# k64f-kit.net
KiCad netlist of a schematic drawn in EAGLE
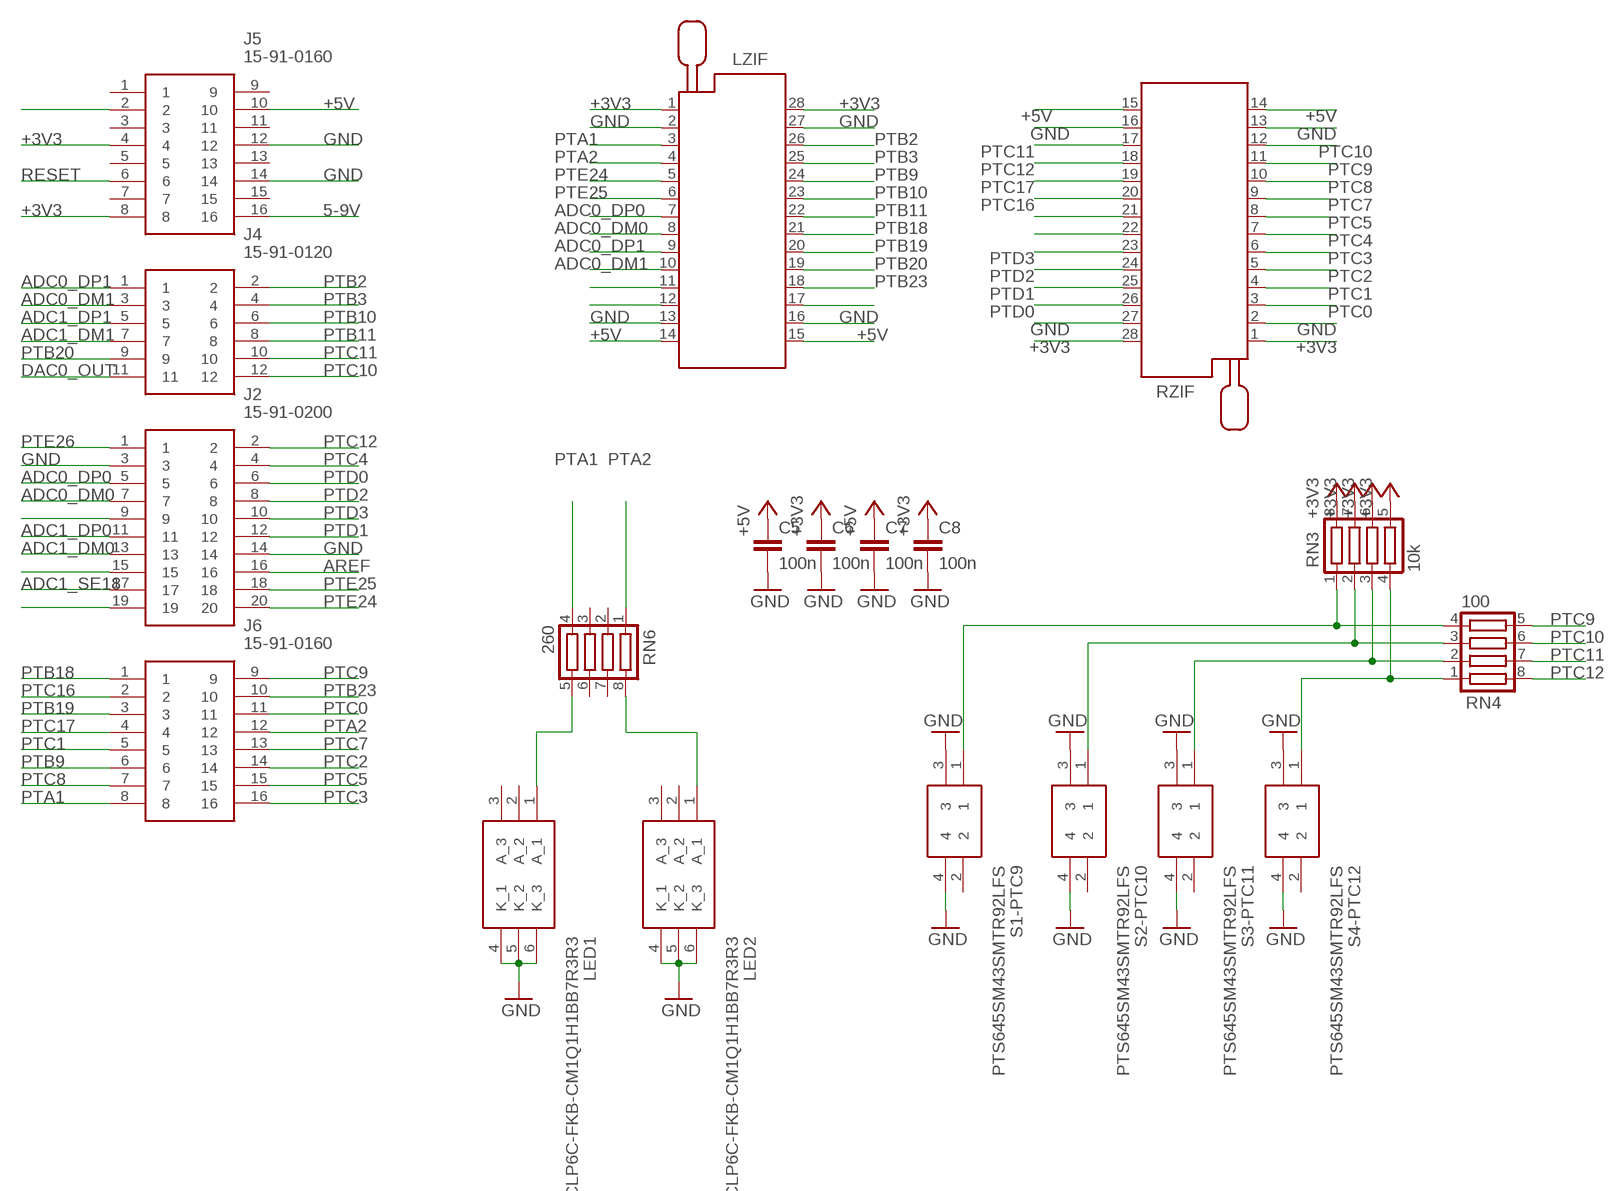
[diagram p0: schematic, sheet 1]

(export (version "E")
  (design (tool "Eeschema 10.0.6"))
  (components
    (comp (ref "C5")
      (value "100n")
      (footprint "eagle-import:C1206")
      (libsource (lib "eagle-import") (part "C-EUC1206"))
    )
    (comp (ref "C6")
      (value "100n")
      (footprint "eagle-import:C1206")
      (libsource (lib "eagle-import") (part "C-EUC1206"))
    )
    (comp (ref "C7")
      (value "100n")
      (footprint "eagle-import:C1206")
      (libsource (lib "eagle-import") (part "C-EUC1206"))
    )
    (comp (ref "C8")
      (value "100n")
      (footprint "eagle-import:C1206")
      (libsource (lib "eagle-import") (part "C-EUC1206"))
    )
    (comp (ref "J2")
      (value "15-91-0200")
      (footprint "eagle-import:15910200")
      (fields (field (name "MOUSER_PART_NUMBER") "538-15-91-0200"))
      (libsource (lib "eagle-import") (part "15-91-0200"))
    )
    (comp (ref "J4")
      (value "15-91-0120")
      (footprint "eagle-import:15910120")
      (fields (field (name "MOUSER_PART_NUMBER") "538-15-91-0120"))
      (libsource (lib "eagle-import") (part "15-91-0120"))
    )
    (comp (ref "J5")
      (value "15-91-0160")
      (footprint "eagle-import:15910160")
      (fields
        (field (name "MANUFACTURER_PART_NUMBER") "15-91-2160")
        (field (name "MOUSER_PART_NUMBER") "538-15-91-2160")
      )
      (libsource (lib "eagle-import") (part "15-91-0160"))
    )
    (comp (ref "J6")
      (value "15-91-0160")
      (footprint "eagle-import:15910160")
      (fields
        (field (name "MANUFACTURER_PART_NUMBER") "15-91-2160")
        (field (name "MOUSER_PART_NUMBER") "538-15-91-2160")
      )
      (libsource (lib "eagle-import") (part "15-91-0160"))
    )
    (comp (ref "LED1")
      (value "CLP6C-FKB-CM1Q1H1BB7R3R3")
      (footprint "eagle-import:CLP6CFKBCM1Q1H1BB7R3R3")
      (fields
        (field (name "MOUSER_PART_NUMBER") "941-P6CFKBCM1Q1H17R3")
        (field (name "RS_PART_NUMBER") "8106939P")
      )
      (libsource (lib "eagle-import") (part "CLP6C-FKB-CM1Q1H1BB7R3R3"))
    )
    (comp (ref "LED2")
      (value "CLP6C-FKB-CM1Q1H1BB7R3R3")
      (footprint "eagle-import:CLP6CFKBCM1Q1H1BB7R3R3")
      (fields
        (field (name "MOUSER_PART_NUMBER") "941-P6CFKBCM1Q1H17R3")
        (field (name "RS_PART_NUMBER") "8106939P")
      )
      (libsource (lib "eagle-import") (part "CLP6C-FKB-CM1Q1H1BB7R3R3"))
    )
    (comp (ref "LZIF")
      (value "228-22-602")
      (footprint "eagle-import:228-1277-00-0602J")
      (libsource (lib "eagle-import") (part "228-?22-602"))
    )
    (comp (ref "RN3")
      (value "10k")
      (footprint "eagle-import:CTS742C083")
      (libsource (lib "eagle-import") (part "CTS742C083"))
    )
    (comp (ref "RN4")
      (value "100")
      (footprint "eagle-import:CTS742C083")
      (libsource (lib "eagle-import") (part "CTS742C083"))
    )
    (comp (ref "RN6")
      (value "260")
      (footprint "eagle-import:CTS742C083")
      (libsource (lib "eagle-import") (part "CTS742C083"))
    )
    (comp (ref "RZIF")
      (value "228-22-602")
      (footprint "eagle-import:228-1277-00-0602J")
      (libsource (lib "eagle-import") (part "228-?22-602"))
    )
    (comp (ref "S1-PTC9")
      (value "PTS645SM43SMTR92LFS")
      (footprint "eagle-import:PTS645(SMT)")
      (fields (field (name "MOUSER_PART_NUMBER") "611-PTS645SM43SMTR92"))
      (libsource (lib "eagle-import") (part "PTS645SM43SMTR92LFS"))
    )
    (comp (ref "S2-PTC10")
      (value "PTS645SM43SMTR92LFS")
      (footprint "eagle-import:PTS645(SMT)")
      (fields (field (name "MOUSER_PART_NUMBER") "611-PTS645SM43SMTR92"))
      (libsource (lib "eagle-import") (part "PTS645SM43SMTR92LFS"))
    )
    (comp (ref "S3-PTC11")
      (value "PTS645SM43SMTR92LFS")
      (footprint "eagle-import:PTS645(SMT)")
      (fields (field (name "MOUSER_PART_NUMBER") "611-PTS645SM43SMTR92"))
      (libsource (lib "eagle-import") (part "PTS645SM43SMTR92LFS"))
    )
    (comp (ref "S4-PTC12")
      (value "PTS645SM43SMTR92LFS")
      (footprint "eagle-import:PTS645(SMT)")
      (fields (field (name "MOUSER_PART_NUMBER") "611-PTS645SM43SMTR92"))
      (libsource (lib "eagle-import") (part "PTS645SM43SMTR92LFS"))
    )
  )
  (nets
    (net (code "1") (name "+3V3") (class "Default")
      (node (ref "C6") (pin "1") (pinfunction "1_1") (pintype "passive"))
      (node (ref "C8") (pin "1") (pinfunction "1_1") (pintype "passive"))
      (node (ref "J5") (pin "4") (pinfunction "4_4") (pintype "bidirectional"))
      (node (ref "J5") (pin "8") (pinfunction "8_8") (pintype "bidirectional"))
      (node (ref "LZIF") (pin "1") (pinfunction "1_1") (pintype "passive"))
      (node (ref "LZIF") (pin "28") (pinfunction "28_28") (pintype "passive"))
      (node (ref "RN3") (pin "5") (pinfunction "5_5") (pintype "passive"))
      (node (ref "RN3") (pin "6") (pinfunction "6_6") (pintype "passive"))
      (node (ref "RN3") (pin "7") (pinfunction "7_7") (pintype "passive"))
      (node (ref "RN3") (pin "8") (pinfunction "8_8") (pintype "passive"))
      (node (ref "RZIF") (pin "1") (pinfunction "1_1") (pintype "passive"))
      (node (ref "RZIF") (pin "28") (pinfunction "28_28") (pintype "passive"))
    )
    (net (code "2") (name "+5V") (class "Default")
      (node (ref "C5") (pin "1") (pinfunction "1_1") (pintype "passive"))
      (node (ref "C7") (pin "1") (pinfunction "1_1") (pintype "passive"))
      (node (ref "J5") (pin "10") (pinfunction "10_10") (pintype "bidirectional"))
      (node (ref "LZIF") (pin "14") (pinfunction "14_14") (pintype "passive"))
      (node (ref "LZIF") (pin "15") (pinfunction "15_15") (pintype "passive"))
      (node (ref "RZIF") (pin "14") (pinfunction "14_14") (pintype "passive"))
      (node (ref "RZIF") (pin "15") (pinfunction "15_15") (pintype "passive"))
    )
    (net (code "3") (name "/5-9V") (class "Default")
      (node (ref "J5") (pin "16") (pinfunction "16_16") (pintype "bidirectional"))
    )
    (net (code "4") (name "/ADC0_DM0") (class "Default")
      (node (ref "J2") (pin "7") (pinfunction "7_7") (pintype "bidirectional"))
      (node (ref "LZIF") (pin "8") (pinfunction "8_8") (pintype "passive"))
    )
    (net (code "5") (name "/ADC0_DM1") (class "Default")
      (node (ref "J4") (pin "3") (pinfunction "3_3") (pintype "bidirectional"))
      (node (ref "LZIF") (pin "10") (pinfunction "10_10") (pintype "passive"))
    )
    (net (code "6") (name "/ADC0_DP0") (class "Default")
      (node (ref "J2") (pin "5") (pinfunction "5_5") (pintype "bidirectional"))
      (node (ref "LZIF") (pin "7") (pinfunction "7_7") (pintype "passive"))
    )
    (net (code "7") (name "/ADC0_DP1") (class "Default")
      (node (ref "J4") (pin "1") (pinfunction "1_1") (pintype "bidirectional"))
      (node (ref "LZIF") (pin "9") (pinfunction "9_9") (pintype "passive"))
    )
    (net (code "8") (name "/ADC1_DM0") (class "Default")
      (node (ref "J2") (pin "13") (pinfunction "13_13") (pintype "bidirectional"))
    )
    (net (code "9") (name "/ADC1_DM1") (class "Default")
      (node (ref "J4") (pin "7") (pinfunction "7_7") (pintype "bidirectional"))
    )
    (net (code "10") (name "/ADC1_DP0") (class "Default")
      (node (ref "J2") (pin "11") (pinfunction "11_11") (pintype "bidirectional"))
    )
    (net (code "11") (name "/ADC1_DP1") (class "Default")
      (node (ref "J4") (pin "5") (pinfunction "5_5") (pintype "bidirectional"))
    )
    (net (code "12") (name "/ADC1_SE18") (class "Default")
      (node (ref "J2") (pin "17") (pinfunction "17_17") (pintype "bidirectional"))
    )
    (net (code "13") (name "/AREF") (class "Default")
      (node (ref "J2") (pin "16") (pinfunction "16_16") (pintype "bidirectional"))
    )
    (net (code "14") (name "/DAC0_OUT") (class "Default")
      (node (ref "J4") (pin "11") (pinfunction "11_11") (pintype "bidirectional"))
    )
    (net (code "15") (name "/PTA1") (class "Default")
      (node (ref "J6") (pin "8") (pinfunction "8_8") (pintype "bidirectional"))
      (node (ref "LZIF") (pin "3") (pinfunction "3_3") (pintype "passive"))
      (node (ref "RN6") (pin "1") (pinfunction "1_1") (pintype "passive"))
    )
    (net (code "16") (name "/PTA2") (class "Default")
      (node (ref "J6") (pin "12") (pinfunction "12_12") (pintype "bidirectional"))
      (node (ref "LZIF") (pin "4") (pinfunction "4_4") (pintype "passive"))
      (node (ref "RN6") (pin "4") (pinfunction "4_4") (pintype "passive"))
    )
    (net (code "17") (name "/PTB2") (class "Default")
      (node (ref "J4") (pin "2") (pinfunction "2_2") (pintype "bidirectional"))
      (node (ref "LZIF") (pin "26") (pinfunction "26_26") (pintype "passive"))
    )
    (net (code "18") (name "/PTB3") (class "Default")
      (node (ref "J4") (pin "4") (pinfunction "4_4") (pintype "bidirectional"))
      (node (ref "LZIF") (pin "25") (pinfunction "25_25") (pintype "passive"))
    )
    (net (code "19") (name "/PTB9") (class "Default")
      (node (ref "J6") (pin "6") (pinfunction "6_6") (pintype "bidirectional"))
      (node (ref "LZIF") (pin "24") (pinfunction "24_24") (pintype "passive"))
    )
    (net (code "20") (name "/PTB10") (class "Default")
      (node (ref "J4") (pin "6") (pinfunction "6_6") (pintype "bidirectional"))
      (node (ref "LZIF") (pin "23") (pinfunction "23_23") (pintype "passive"))
    )
    (net (code "21") (name "/PTB11") (class "Default")
      (node (ref "J4") (pin "8") (pinfunction "8_8") (pintype "bidirectional"))
      (node (ref "LZIF") (pin "22") (pinfunction "22_22") (pintype "passive"))
    )
    (net (code "22") (name "/PTB18") (class "Default")
      (node (ref "J6") (pin "1") (pinfunction "1_1") (pintype "bidirectional"))
      (node (ref "LZIF") (pin "21") (pinfunction "21_21") (pintype "passive"))
    )
    (net (code "23") (name "/PTB19") (class "Default")
      (node (ref "J6") (pin "3") (pinfunction "3_3") (pintype "bidirectional"))
      (node (ref "LZIF") (pin "20") (pinfunction "20_20") (pintype "passive"))
    )
    (net (code "24") (name "/PTB20") (class "Default")
      (node (ref "J4") (pin "9") (pinfunction "9_9") (pintype "bidirectional"))
      (node (ref "LZIF") (pin "19") (pinfunction "19_19") (pintype "passive"))
    )
    (net (code "25") (name "/PTB23") (class "Default")
      (node (ref "J6") (pin "10") (pinfunction "10_10") (pintype "bidirectional"))
      (node (ref "LZIF") (pin "18") (pinfunction "18_18") (pintype "passive"))
    )
    (net (code "26") (name "/PTC0") (class "Default")
      (node (ref "J6") (pin "11") (pinfunction "11_11") (pintype "bidirectional"))
      (node (ref "RZIF") (pin "3") (pinfunction "3_3") (pintype "passive"))
    )
    (net (code "27") (name "/PTC1") (class "Default")
      (node (ref "J6") (pin "5") (pinfunction "5_5") (pintype "bidirectional"))
      (node (ref "RZIF") (pin "4") (pinfunction "4_4") (pintype "passive"))
    )
    (net (code "28") (name "/PTC2") (class "Default")
      (node (ref "J6") (pin "14") (pinfunction "14_14") (pintype "bidirectional"))
      (node (ref "RZIF") (pin "5") (pinfunction "5_5") (pintype "passive"))
    )
    (net (code "29") (name "/PTC3") (class "Default")
      (node (ref "J6") (pin "16") (pinfunction "16_16") (pintype "bidirectional"))
      (node (ref "RZIF") (pin "6") (pinfunction "6_6") (pintype "passive"))
    )
    (net (code "30") (name "/PTC4") (class "Default")
      (node (ref "J2") (pin "4") (pinfunction "4_4") (pintype "bidirectional"))
      (node (ref "RZIF") (pin "7") (pinfunction "7_7") (pintype "passive"))
    )
    (net (code "31") (name "/PTC5") (class "Default")
      (node (ref "J6") (pin "15") (pinfunction "15_15") (pintype "bidirectional"))
      (node (ref "RZIF") (pin "8") (pinfunction "8_8") (pintype "passive"))
    )
    (net (code "32") (name "/PTC7") (class "Default")
      (node (ref "J6") (pin "13") (pinfunction "13_13") (pintype "bidirectional"))
      (node (ref "RZIF") (pin "9") (pinfunction "9_9") (pintype "passive"))
    )
    (net (code "33") (name "/PTC8") (class "Default")
      (node (ref "J6") (pin "7") (pinfunction "7_7") (pintype "bidirectional"))
      (node (ref "RZIF") (pin "10") (pinfunction "10_10") (pintype "passive"))
    )
    (net (code "34") (name "/PTC9") (class "Default")
      (node (ref "J6") (pin "9") (pinfunction "9_9") (pintype "bidirectional"))
      (node (ref "RN4") (pin "5") (pinfunction "5_5") (pintype "passive"))
      (node (ref "RZIF") (pin "11") (pinfunction "11_11") (pintype "passive"))
    )
    (net (code "35") (name "/PTC10") (class "Default")
      (node (ref "J4") (pin "12") (pinfunction "12_12") (pintype "bidirectional"))
      (node (ref "RN4") (pin "6") (pinfunction "6_6") (pintype "passive"))
      (node (ref "RZIF") (pin "12") (pinfunction "12_12") (pintype "passive"))
    )
    (net (code "36") (name "/PTC11") (class "Default")
      (node (ref "J4") (pin "10") (pinfunction "10_10") (pintype "bidirectional"))
      (node (ref "RN4") (pin "7") (pinfunction "7_7") (pintype "passive"))
      (node (ref "RZIF") (pin "17") (pinfunction "17_17") (pintype "passive"))
    )
    (net (code "37") (name "/PTC12") (class "Default")
      (node (ref "J2") (pin "2") (pinfunction "2_2") (pintype "bidirectional"))
      (node (ref "RN4") (pin "8") (pinfunction "8_8") (pintype "passive"))
      (node (ref "RZIF") (pin "18") (pinfunction "18_18") (pintype "passive"))
    )
    (net (code "38") (name "/PTC16") (class "Default")
      (node (ref "J6") (pin "2") (pinfunction "2_2") (pintype "bidirectional"))
      (node (ref "RZIF") (pin "20") (pinfunction "20_20") (pintype "passive"))
    )
    (net (code "39") (name "/PTC17") (class "Default")
      (node (ref "J6") (pin "4") (pinfunction "4_4") (pintype "bidirectional"))
      (node (ref "RZIF") (pin "19") (pinfunction "19_19") (pintype "passive"))
    )
    (net (code "40") (name "/PTD0") (class "Default")
      (node (ref "J2") (pin "6") (pinfunction "6_6") (pintype "bidirectional"))
      (node (ref "RZIF") (pin "26") (pinfunction "26_26") (pintype "passive"))
    )
    (net (code "41") (name "/PTD1") (class "Default")
      (node (ref "J2") (pin "12") (pinfunction "12_12") (pintype "bidirectional"))
      (node (ref "RZIF") (pin "25") (pinfunction "25_25") (pintype "passive"))
    )
    (net (code "42") (name "/PTD2") (class "Default")
      (node (ref "J2") (pin "8") (pinfunction "8_8") (pintype "bidirectional"))
      (node (ref "RZIF") (pin "24") (pinfunction "24_24") (pintype "passive"))
    )
    (net (code "43") (name "/PTD3") (class "Default")
      (node (ref "J2") (pin "10") (pinfunction "10_10") (pintype "bidirectional"))
      (node (ref "RZIF") (pin "23") (pinfunction "23_23") (pintype "passive"))
    )
    (net (code "44") (name "/PTE24") (class "Default")
      (node (ref "J2") (pin "20") (pinfunction "20_20") (pintype "bidirectional"))
      (node (ref "LZIF") (pin "5") (pinfunction "5_5") (pintype "passive"))
    )
    (net (code "45") (name "/PTE25") (class "Default")
      (node (ref "J2") (pin "18") (pinfunction "18_18") (pintype "bidirectional"))
      (node (ref "LZIF") (pin "6") (pinfunction "6_6") (pintype "passive"))
    )
    (net (code "46") (name "/PTE26") (class "Default")
      (node (ref "J2") (pin "1") (pinfunction "1_1") (pintype "bidirectional"))
    )
    (net (code "47") (name "/RESET") (class "Default")
      (node (ref "J5") (pin "6") (pinfunction "6_6") (pintype "bidirectional"))
    )
    (net (code "48") (name "GND") (class "Default")
      (node (ref "C5") (pin "2") (pinfunction "2_2") (pintype "passive"))
      (node (ref "C6") (pin "2") (pinfunction "2_2") (pintype "passive"))
      (node (ref "C7") (pin "2") (pinfunction "2_2") (pintype "passive"))
      (node (ref "C8") (pin "2") (pinfunction "2_2") (pintype "passive"))
      (node (ref "J2") (pin "14") (pinfunction "14_14") (pintype "bidirectional"))
      (node (ref "J2") (pin "3") (pinfunction "3_3") (pintype "bidirectional"))
      (node (ref "J5") (pin "12") (pinfunction "12_12") (pintype "bidirectional"))
      (node (ref "J5") (pin "14") (pinfunction "14_14") (pintype "bidirectional"))
      (node (ref "LED1") (pin "4") (pinfunction "K_1_4") (pintype "bidirectional"))
      (node (ref "LED1") (pin "5") (pinfunction "K_2_5") (pintype "bidirectional"))
      (node (ref "LED1") (pin "6") (pinfunction "K_3_6") (pintype "bidirectional"))
      (node (ref "LED2") (pin "4") (pinfunction "K_1_4") (pintype "bidirectional"))
      (node (ref "LED2") (pin "5") (pinfunction "K_2_5") (pintype "bidirectional"))
      (node (ref "LED2") (pin "6") (pinfunction "K_3_6") (pintype "bidirectional"))
      (node (ref "LZIF") (pin "13") (pinfunction "13_13") (pintype "passive"))
      (node (ref "LZIF") (pin "16") (pinfunction "16_16") (pintype "passive"))
      (node (ref "LZIF") (pin "2") (pinfunction "2_2") (pintype "passive"))
      (node (ref "LZIF") (pin "27") (pinfunction "27_27") (pintype "passive"))
      (node (ref "RZIF") (pin "13") (pinfunction "13_13") (pintype "passive"))
      (node (ref "RZIF") (pin "16") (pinfunction "16_16") (pintype "passive"))
      (node (ref "RZIF") (pin "2") (pinfunction "2_2") (pintype "passive"))
      (node (ref "RZIF") (pin "27") (pinfunction "27_27") (pintype "passive"))
      (node (ref "S1-PTC9") (pin "3") (pinfunction "3_3") (pintype "bidirectional"))
      (node (ref "S1-PTC9") (pin "4") (pinfunction "4_4") (pintype "bidirectional"))
      (node (ref "S2-PTC10") (pin "3") (pinfunction "3_3") (pintype "bidirectional"))
      (node (ref "S2-PTC10") (pin "4") (pinfunction "4_4") (pintype "bidirectional"))
      (node (ref "S3-PTC11") (pin "3") (pinfunction "3_3") (pintype "bidirectional"))
      (node (ref "S3-PTC11") (pin "4") (pinfunction "4_4") (pintype "bidirectional"))
      (node (ref "S4-PTC12") (pin "3") (pinfunction "3_3") (pintype "bidirectional"))
      (node (ref "S4-PTC12") (pin "4") (pinfunction "4_4") (pintype "bidirectional"))
    )
    (net (code "49") (name "Net-(LED1-A_1)") (class "Default")
      (node (ref "LED1") (pin "1") (pinfunction "A_1_1") (pintype "bidirectional"))
      (node (ref "RN6") (pin "5") (pinfunction "5_5") (pintype "passive"))
    )
    (net (code "50") (name "Net-(LED2-A_1)") (class "Default")
      (node (ref "LED2") (pin "1") (pinfunction "A_1_1") (pintype "bidirectional"))
      (node (ref "RN6") (pin "8") (pinfunction "8_8") (pintype "passive"))
    )
    (net (code "51") (name "Net-(RN3-Pad1)") (class "Default")
      (node (ref "RN3") (pin "1") (pinfunction "1_1") (pintype "passive"))
      (node (ref "RN4") (pin "4") (pinfunction "4_4") (pintype "passive"))
      (node (ref "S1-PTC9") (pin "1") (pinfunction "1_1") (pintype "bidirectional"))
    )
    (net (code "52") (name "Net-(RN3-Pad2)") (class "Default")
      (node (ref "RN3") (pin "2") (pinfunction "2_2") (pintype "passive"))
      (node (ref "RN4") (pin "3") (pinfunction "3_3") (pintype "passive"))
      (node (ref "S2-PTC10") (pin "1") (pinfunction "1_1") (pintype "bidirectional"))
    )
    (net (code "53") (name "Net-(RN3-Pad3)") (class "Default")
      (node (ref "RN3") (pin "3") (pinfunction "3_3") (pintype "passive"))
      (node (ref "RN4") (pin "2") (pinfunction "2_2") (pintype "passive"))
      (node (ref "S3-PTC11") (pin "1") (pinfunction "1_1") (pintype "bidirectional"))
    )
    (net (code "54") (name "Net-(RN3-Pad4)") (class "Default")
      (node (ref "RN3") (pin "4") (pinfunction "4_4") (pintype "passive"))
      (node (ref "RN4") (pin "1") (pinfunction "1_1") (pintype "passive"))
      (node (ref "S4-PTC12") (pin "1") (pinfunction "1_1") (pintype "bidirectional"))
    )
    (net (code "55") (name "unconnected-(J2-Pad9)") (class "Default")
      (node (ref "J2") (pin "9") (pinfunction "9_9") (pintype "bidirectional"))
    )
    (net (code "56") (name "unconnected-(J2-Pad15)") (class "Default")
      (node (ref "J2") (pin "15") (pinfunction "15_15") (pintype "bidirectional"))
    )
    (net (code "57") (name "unconnected-(J2-Pad19)") (class "Default")
      (node (ref "J2") (pin "19") (pinfunction "19_19") (pintype "bidirectional"))
    )
    (net (code "58") (name "unconnected-(J5-Pad1)") (class "Default")
      (node (ref "J5") (pin "1") (pinfunction "1_1") (pintype "bidirectional"))
    )
    (net (code "59") (name "unconnected-(J5-Pad2)") (class "Default")
      (node (ref "J5") (pin "2") (pinfunction "2_2") (pintype "bidirectional"))
    )
    (net (code "60") (name "unconnected-(J5-Pad3)") (class "Default")
      (node (ref "J5") (pin "3") (pinfunction "3_3") (pintype "bidirectional"))
    )
    (net (code "61") (name "unconnected-(J5-Pad5)") (class "Default")
      (node (ref "J5") (pin "5") (pinfunction "5_5") (pintype "bidirectional"))
    )
    (net (code "62") (name "unconnected-(J5-Pad7)") (class "Default")
      (node (ref "J5") (pin "7") (pinfunction "7_7") (pintype "bidirectional"))
    )
    (net (code "63") (name "unconnected-(J5-Pad9)") (class "Default")
      (node (ref "J5") (pin "9") (pinfunction "9_9") (pintype "bidirectional"))
    )
    (net (code "64") (name "unconnected-(J5-Pad11)") (class "Default")
      (node (ref "J5") (pin "11") (pinfunction "11_11") (pintype "bidirectional"))
    )
    (net (code "65") (name "unconnected-(J5-Pad13)") (class "Default")
      (node (ref "J5") (pin "13") (pinfunction "13_13") (pintype "bidirectional"))
    )
    (net (code "66") (name "unconnected-(J5-Pad15)") (class "Default")
      (node (ref "J5") (pin "15") (pinfunction "15_15") (pintype "bidirectional"))
    )
    (net (code "67") (name "unconnected-(LED1-A_2-Pad2)") (class "Default")
      (node (ref "LED1") (pin "2") (pinfunction "A_2_2") (pintype "bidirectional"))
    )
    (net (code "68") (name "unconnected-(LED1-A_3-Pad3)") (class "Default")
      (node (ref "LED1") (pin "3") (pinfunction "A_3_3") (pintype "bidirectional"))
    )
    (net (code "69") (name "unconnected-(LED2-A_2-Pad2)") (class "Default")
      (node (ref "LED2") (pin "2") (pinfunction "A_2_2") (pintype "bidirectional"))
    )
    (net (code "70") (name "unconnected-(LED2-A_3-Pad3)") (class "Default")
      (node (ref "LED2") (pin "3") (pinfunction "A_3_3") (pintype "bidirectional"))
    )
    (net (code "71") (name "unconnected-(LZIF-Pad11)") (class "Default")
      (node (ref "LZIF") (pin "11") (pinfunction "11_11") (pintype "passive"))
    )
    (net (code "72") (name "unconnected-(LZIF-Pad12)") (class "Default")
      (node (ref "LZIF") (pin "12") (pinfunction "12_12") (pintype "passive"))
    )
    (net (code "73") (name "unconnected-(LZIF-Pad17)") (class "Default")
      (node (ref "LZIF") (pin "17") (pinfunction "17_17") (pintype "passive"))
    )
    (net (code "74") (name "unconnected-(RN6-Pad2)") (class "Default")
      (node (ref "RN6") (pin "2") (pinfunction "2_2") (pintype "passive"))
    )
    (net (code "75") (name "unconnected-(RN6-Pad3)") (class "Default")
      (node (ref "RN6") (pin "3") (pinfunction "3_3") (pintype "passive"))
    )
    (net (code "76") (name "unconnected-(RN6-Pad6)") (class "Default")
      (node (ref "RN6") (pin "6") (pinfunction "6_6") (pintype "passive"))
    )
    (net (code "77") (name "unconnected-(RN6-Pad7)") (class "Default")
      (node (ref "RN6") (pin "7") (pinfunction "7_7") (pintype "passive"))
    )
    (net (code "78") (name "unconnected-(RZIF-Pad21)") (class "Default")
      (node (ref "RZIF") (pin "21") (pinfunction "21_21") (pintype "passive"))
    )
    (net (code "79") (name "unconnected-(RZIF-Pad22)") (class "Default")
      (node (ref "RZIF") (pin "22") (pinfunction "22_22") (pintype "passive"))
    )
    (net (code "80") (name "unconnected-(S1-PTC9-Pad2)") (class "Default")
      (node (ref "S1-PTC9") (pin "2") (pinfunction "2_2") (pintype "bidirectional"))
    )
    (net (code "81") (name "unconnected-(S2-PTC10-Pad2)") (class "Default")
      (node (ref "S2-PTC10") (pin "2") (pinfunction "2_2") (pintype "bidirectional"))
    )
    (net (code "82") (name "unconnected-(S3-PTC11-Pad2)") (class "Default")
      (node (ref "S3-PTC11") (pin "2") (pinfunction "2_2") (pintype "bidirectional"))
    )
    (net (code "83") (name "unconnected-(S4-PTC12-Pad2)") (class "Default")
      (node (ref "S4-PTC12") (pin "2") (pinfunction "2_2") (pintype "bidirectional"))
    )
  )
)
